# Othermill_PCB_Trace_Test.net
KiCad netlist of a schematic drawn in EAGLE
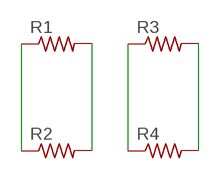
[diagram p0: schematic, sheet 1]

(export (version "E")
  (design (tool "Eeschema 10.0.6"))
  (components
    (comp (ref "R1")
      (value "R-US_0204/2V")
      (footprint "eagle-import:0204V")
      (libsource (lib "eagle-import") (part "R-US_0204/2V"))
    )
    (comp (ref "R2")
      (value "R-US_0204/2V")
      (footprint "eagle-import:0204V")
      (libsource (lib "eagle-import") (part "R-US_0204/2V"))
    )
    (comp (ref "R3")
      (value "R-US_0204/2V")
      (footprint "eagle-import:0204V")
      (libsource (lib "eagle-import") (part "R-US_0204/2V"))
    )
    (comp (ref "R4")
      (value "R-US_0204/2V")
      (footprint "eagle-import:0204V")
      (libsource (lib "eagle-import") (part "R-US_0204/2V"))
    )
  )
  (nets
    (net (code "1") (name "Net-(R1-Pad1)") (class "Default")
      (node (ref "R1") (pin "1") (pinfunction "1_1") (pintype "passive"))
      (node (ref "R2") (pin "1") (pinfunction "1_1") (pintype "passive"))
    )
    (net (code "2") (name "Net-(R1-Pad2)") (class "Default")
      (node (ref "R1") (pin "2") (pinfunction "2_2") (pintype "passive"))
      (node (ref "R2") (pin "2") (pinfunction "2_2") (pintype "passive"))
    )
    (net (code "3") (name "Net-(R3-Pad1)") (class "Default")
      (node (ref "R3") (pin "1") (pinfunction "1_1") (pintype "passive"))
      (node (ref "R4") (pin "1") (pinfunction "1_1") (pintype "passive"))
    )
    (net (code "4") (name "Net-(R3-Pad2)") (class "Default")
      (node (ref "R3") (pin "2") (pinfunction "2_2") (pintype "passive"))
      (node (ref "R4") (pin "2") (pinfunction "2_2") (pintype "passive"))
    )
  )
)
